# SCH_51__2025-06-15.net
KiCad netlist of a schematic drawn in EasyEDA
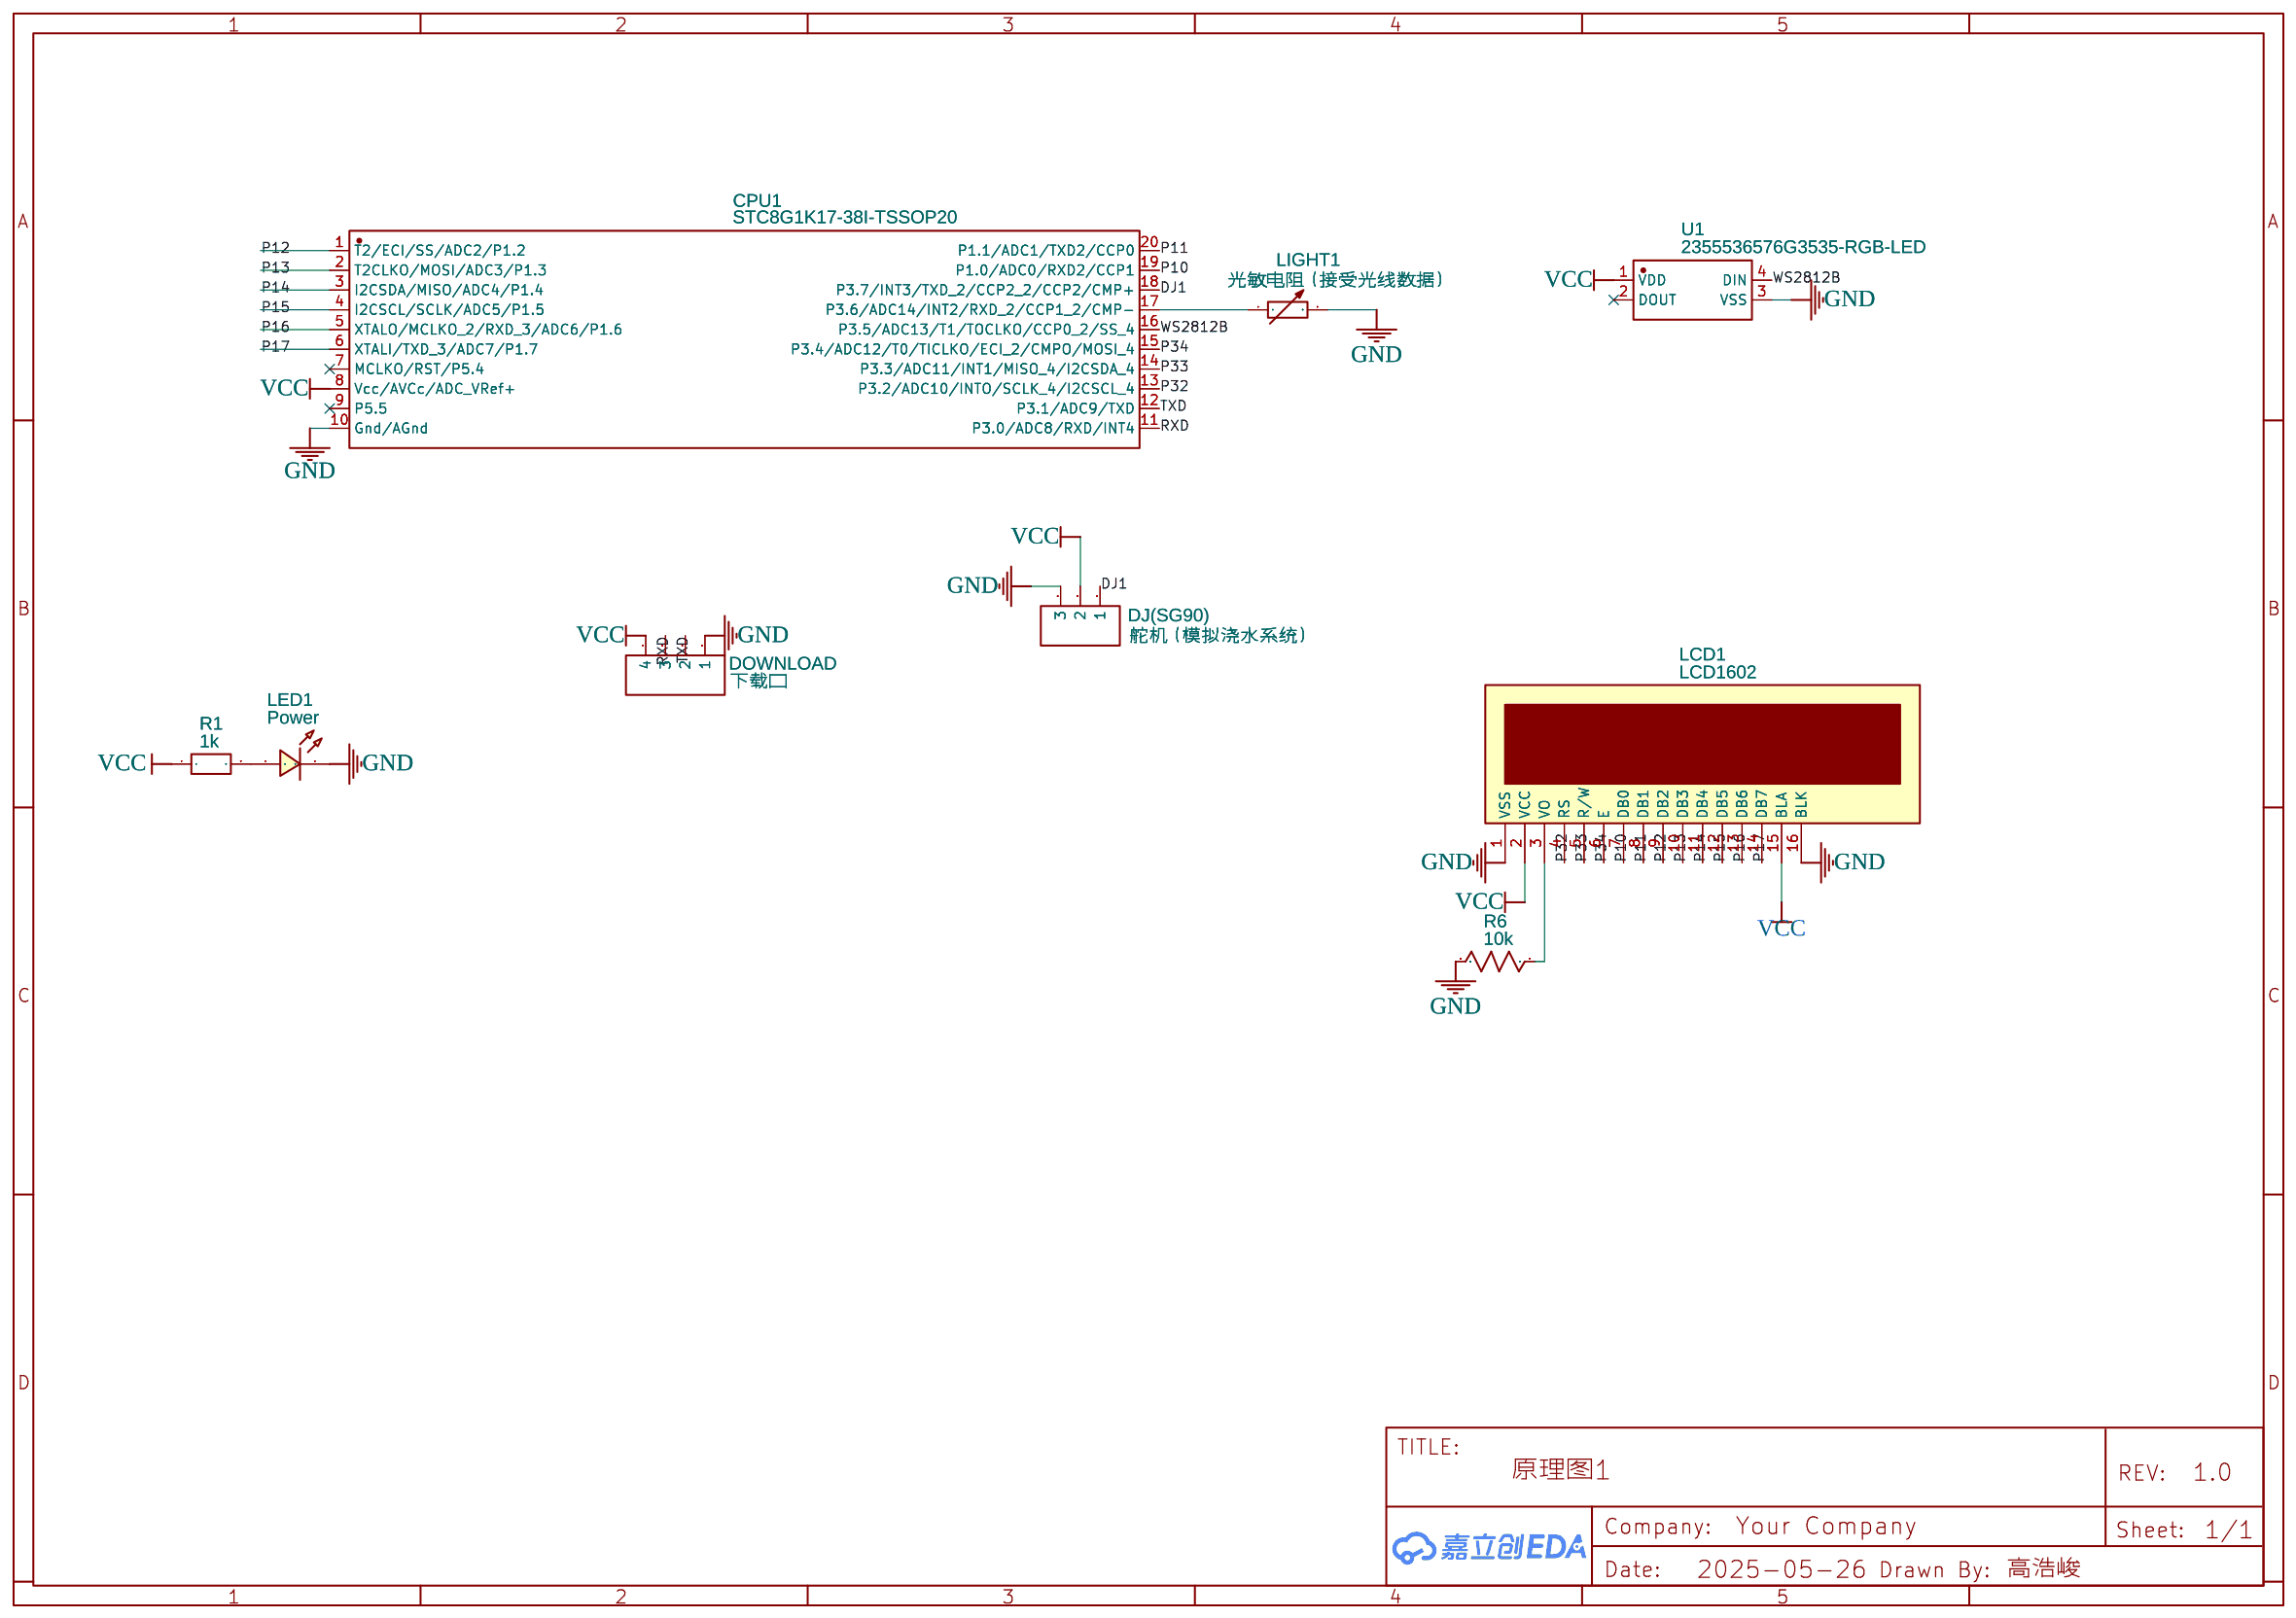
[diagram p0: schematic sheet]

(export (version "E")
  (design (tool "Eeschema 10.0.6"))
  (components
    (comp (ref "CPU1")
      (value "STC8G1K17-38I-TSSOP20")
      (fields (field (name "Manufacturer") "STC"))
      (libsource (lib "") (part "STC8G1K17-38I-TSSOP20"))
    )
    (comp (ref "DJ(SG90)") (value "舵机（模拟浇水系统）") (libsource (lib "") (part "HDR-F-2.54_1x3")))
    (comp (ref "DOWNLOAD") (value "下载口") (libsource (lib "") (part "HDR-F-2.54_1x4")))
    (comp (ref "LCD1")
      (value "LCD1602")
      (fields
        (field (name "Manufacturer Part") "LCM1602K-NSW-BBW")
        (field (name "Manufacturer") "LONTECH(厦门龙特)")
      )
      (libsource (lib "") (part "LCD1602"))
    )
    (comp (ref "LED1")
      (value "Power")
      (fields
        (field (name "Manufacturer Part") "19-217/R6C-AL1M2VY/3T")
        (field (name "Manufacturer") "EVERLIGHT(台湾亿光)")
      )
      (libsource (lib "") (part "LED-0603_R"))
    )
    (comp (ref "LIGHT1")
      (value "光敏电阻（接受光线数据）")
      (fields (field (name "Manufacturer Part") "光敏电阻-5MM"))
      (libsource (lib "") (part "光敏电阻-5MM"))
    )
    (comp (ref "R1") (value "1k") (libsource (lib "") (part "R_0603_EU")))
    (comp (ref "R6") (value "10k") (libsource (lib "") (part "R_0805_US")))
    (comp (ref "U1") (value "2355536576G3535-RGB-LED") (libsource (lib "") (part "2355536576G3535-RGB-LED")))
  )
  (nets
    (net (code "1") (name "/DJ1") (class "Default")
      (node (ref "CPU1") (pin "18") (pinfunction "P3.7/INT3/TXD_2/CCP2_2/CCP2/CMP+_18") (pintype "unspecified"))
      (node (ref "DJ(SG90)") (pin "1") (pinfunction "1_1") (pintype "input"))
    )
    (net (code "2") (name "/P10") (class "Default")
      (node (ref "CPU1") (pin "19") (pinfunction "P1.0/ADC0/RXD2/CCP1_19") (pintype "unspecified"))
      (node (ref "LCD1") (pin "7") (pinfunction "DB0_7") (pintype "unspecified"))
    )
    (net (code "3") (name "/P11") (class "Default")
      (node (ref "CPU1") (pin "20") (pinfunction "P1.1/ADC1/TXD2/CCP0_20") (pintype "unspecified"))
      (node (ref "LCD1") (pin "8") (pinfunction "DB1_8") (pintype "unspecified"))
    )
    (net (code "4") (name "/P12") (class "Default")
      (node (ref "CPU1") (pin "1") (pinfunction "T2/ECI/SS/ADC2/P1.2_1") (pintype "unspecified"))
      (node (ref "LCD1") (pin "9") (pinfunction "DB2_9") (pintype "unspecified"))
    )
    (net (code "5") (name "/P13") (class "Default")
      (node (ref "CPU1") (pin "2") (pinfunction "T2CLKO/MOSI/ADC3/P1.3_2") (pintype "unspecified"))
      (node (ref "LCD1") (pin "10") (pinfunction "DB3_10") (pintype "unspecified"))
    )
    (net (code "6") (name "/P14") (class "Default")
      (node (ref "CPU1") (pin "3") (pinfunction "I2CSDA/MISO/ADC4/P1.4_3") (pintype "unspecified"))
      (node (ref "LCD1") (pin "11") (pinfunction "DB4_11") (pintype "unspecified"))
    )
    (net (code "7") (name "/P15") (class "Default")
      (node (ref "CPU1") (pin "4") (pinfunction "I2CSCL/SCLK/ADC5/P1.5_4") (pintype "unspecified"))
      (node (ref "LCD1") (pin "12") (pinfunction "DB5_12") (pintype "unspecified"))
    )
    (net (code "8") (name "/P16") (class "Default")
      (node (ref "CPU1") (pin "5") (pinfunction "XTALO/MCLKO_2/RXD_3/ADC6/P1.6_5") (pintype "unspecified"))
      (node (ref "LCD1") (pin "13") (pinfunction "DB6_13") (pintype "unspecified"))
    )
    (net (code "9") (name "/P17") (class "Default")
      (node (ref "CPU1") (pin "6") (pinfunction "XTALI/TXD_3/ADC7/P1.7_6") (pintype "unspecified"))
      (node (ref "LCD1") (pin "14") (pinfunction "DB7_14") (pintype "unspecified"))
    )
    (net (code "10") (name "/P32") (class "Default")
      (node (ref "CPU1") (pin "13") (pinfunction "P3.2/ADC10/INTO/SCLK_4/I2CSCL_4_13") (pintype "unspecified"))
      (node (ref "LCD1") (pin "4") (pinfunction "RS_4") (pintype "unspecified"))
    )
    (net (code "11") (name "/P33") (class "Default")
      (node (ref "CPU1") (pin "14") (pinfunction "P3.3/ADC11/INT1/MISO_4/I2CSDA_4_14") (pintype "unspecified"))
      (node (ref "LCD1") (pin "5") (pinfunction "R/W_5") (pintype "unspecified"))
    )
    (net (code "12") (name "/P34") (class "Default")
      (node (ref "CPU1") (pin "15") (pinfunction "P3.4/ADC12/T0/TICLKO/ECI_2/CMPO/MOSI_4_15") (pintype "unspecified"))
      (node (ref "LCD1") (pin "6") (pinfunction "E_6") (pintype "unspecified"))
    )
    (net (code "13") (name "/RXD") (class "Default")
      (node (ref "CPU1") (pin "11") (pinfunction "P3.0/ADC8/RXD/INT4_11") (pintype "unspecified"))
      (node (ref "DOWNLOAD") (pin "3") (pinfunction "3_3") (pintype "unspecified"))
    )
    (net (code "14") (name "/TXD") (class "Default")
      (node (ref "CPU1") (pin "12") (pinfunction "P3.1/ADC9/TXD_12") (pintype "unspecified"))
      (node (ref "DOWNLOAD") (pin "2") (pinfunction "2_2") (pintype "unspecified"))
    )
    (net (code "15") (name "/WS2812B") (class "Default")
      (node (ref "CPU1") (pin "16") (pinfunction "P3.5/ADC13/T1/TOCLKO/CCP0_2/SS_4_16") (pintype "unspecified"))
      (node (ref "U1") (pin "4") (pinfunction "DIN_4") (pintype "unspecified"))
    )
    (net (code "16") (name "GND") (class "Default")
      (node (ref "CPU1") (pin "10") (pinfunction "Gnd/AGnd_10") (pintype "unspecified"))
      (node (ref "DJ(SG90)") (pin "3") (pinfunction "3_3") (pintype "input"))
      (node (ref "DOWNLOAD") (pin "1") (pinfunction "1_1") (pintype "unspecified"))
      (node (ref "LCD1") (pin "1") (pinfunction "VSS_1") (pintype "unspecified"))
      (node (ref "LCD1") (pin "16") (pinfunction "BLK_16") (pintype "unspecified"))
      (node (ref "LED1") (pin "2") (pinfunction "2_2") (pintype "unspecified"))
      (node (ref "LIGHT1") (pin "2") (pinfunction "2_2") (pintype "unspecified"))
      (node (ref "R6") (pin "2") (pinfunction "2_2") (pintype "unspecified"))
      (node (ref "U1") (pin "3") (pinfunction "VSS_3") (pintype "unspecified"))
    )
    (net (code "17") (name "Net-(CPU1-P3.6{slash}ADC14{slash}INT2{slash}RXD_2{slash}CCP1_2{slash}CMP-)") (class "Default")
      (node (ref "CPU1") (pin "17") (pinfunction "P3.6/ADC14/INT2/RXD_2/CCP1_2/CMP-_17") (pintype "unspecified"))
      (node (ref "LIGHT1") (pin "1") (pinfunction "1_1") (pintype "unspecified"))
    )
    (net (code "18") (name "Net-(LCD1-VO)") (class "Default")
      (node (ref "LCD1") (pin "3") (pinfunction "VO_3") (pintype "unspecified"))
      (node (ref "R6") (pin "1") (pinfunction "1_1") (pintype "unspecified"))
    )
    (net (code "19") (name "Net-(LED1-Pad1)") (class "Default")
      (node (ref "LED1") (pin "1") (pinfunction "1_1") (pintype "unspecified"))
      (node (ref "R1") (pin "2") (pinfunction "2_2") (pintype "unspecified"))
    )
    (net (code "20") (name "VCC") (class "Default")
      (node (ref "CPU1") (pin "8") (pinfunction "Vcc/AVCc/ADC_VRef+_8") (pintype "unspecified"))
      (node (ref "DJ(SG90)") (pin "2") (pinfunction "2_2") (pintype "input"))
      (node (ref "DOWNLOAD") (pin "4") (pinfunction "4_4") (pintype "unspecified"))
      (node (ref "LCD1") (pin "15") (pinfunction "BLA_15") (pintype "unspecified"))
      (node (ref "LCD1") (pin "2") (pinfunction "VCC_2") (pintype "unspecified"))
      (node (ref "R1") (pin "1") (pinfunction "1_1") (pintype "unspecified"))
      (node (ref "U1") (pin "1") (pinfunction "VDD_1") (pintype "unspecified"))
    )
    (net (code "21") (name "unconnected-(CPU1-MCLKO{slash}RST{slash}P5.4-Pad7)") (class "Default")
      (node (ref "CPU1") (pin "7") (pinfunction "MCLKO/RST/P5.4_7") (pintype "unspecified+no_connect"))
    )
    (net (code "22") (name "unconnected-(CPU1-P5.5-Pad9)") (class "Default")
      (node (ref "CPU1") (pin "9") (pinfunction "P5.5_9") (pintype "unspecified+no_connect"))
    )
    (net (code "23") (name "unconnected-(U1-DOUT-Pad2)") (class "Default")
      (node (ref "U1") (pin "2") (pinfunction "DOUT_2") (pintype "unspecified+no_connect"))
    )
  )
)
